# module.net
KiCad netlist of a schematic drawn in EAGLE
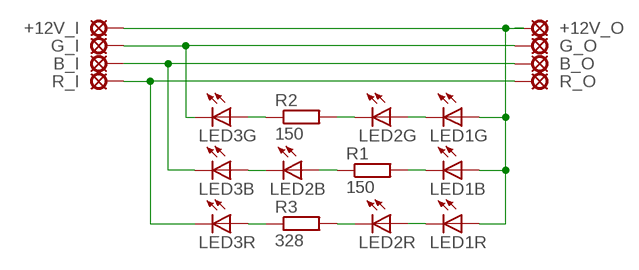
[diagram p0: schematic, sheet 1]

(export (version "E")
  (design (tool "Eeschema 10.0.6"))
  (components
    (comp (ref "+12V_I")
      (value "LSP10")
      (footprint "eagle-import:LSP10")
      (libsource (lib "eagle-import") (part "LSP10"))
    )
    (comp (ref "+12V_O")
      (value "LSP10")
      (footprint "eagle-import:LSP10")
      (libsource (lib "eagle-import") (part "LSP10"))
    )
    (comp (ref "B_I")
      (value "LSP10")
      (footprint "eagle-import:LSP10")
      (libsource (lib "eagle-import") (part "LSP10"))
    )
    (comp (ref "B_O")
      (value "LSP10")
      (footprint "eagle-import:LSP10")
      (libsource (lib "eagle-import") (part "LSP10"))
    )
    (comp (ref "G_I")
      (value "LSP10")
      (footprint "eagle-import:LSP10")
      (libsource (lib "eagle-import") (part "LSP10"))
    )
    (comp (ref "G_O")
      (value "LSP10")
      (footprint "eagle-import:LSP10")
      (libsource (lib "eagle-import") (part "LSP10"))
    )
    (comp (ref "LED1")
      (value "GM5WA94310A")
      (footprint "eagle-import:GM5WA94310A")
      (libsource (lib "eagle-import") (part "GM5WA94310A"))
    )
    (comp (ref "LED2")
      (value "GM5WA94310A")
      (footprint "eagle-import:GM5WA94310A")
      (libsource (lib "eagle-import") (part "GM5WA94310A"))
    )
    (comp (ref "LED3")
      (value "GM5WA94310A")
      (footprint "eagle-import:GM5WA94310A")
      (libsource (lib "eagle-import") (part "GM5WA94310A"))
    )
    (comp (ref "R1")
      (value "150")
      (footprint "eagle-import:M1206")
      (libsource (lib "eagle-import") (part "R-EU_M1206"))
    )
    (comp (ref "R2")
      (value "150")
      (footprint "eagle-import:M1206")
      (libsource (lib "eagle-import") (part "R-EU_M1206"))
    )
    (comp (ref "R3")
      (value "328")
      (footprint "eagle-import:M1206")
      (libsource (lib "eagle-import") (part "R-EU_M1206"))
    )
    (comp (ref "R_I")
      (value "LSP10")
      (footprint "eagle-import:LSP10")
      (libsource (lib "eagle-import") (part "LSP10"))
    )
    (comp (ref "R_O")
      (value "LSP10")
      (footprint "eagle-import:LSP10")
      (libsource (lib "eagle-import") (part "LSP10"))
    )
  )
  (nets
    (net (code "1") (name "Net-(LED1A-A)") (class "Default")
      (node (ref "+12V_I") (pin "MP") (pinfunction "MP_MP") (pintype "passive"))
      (node (ref "+12V_O") (pin "MP") (pinfunction "MP_MP") (pintype "passive"))
      (node (ref "LED1") (pin "1") (pinfunction "A_1") (pintype "passive"))
      (node (ref "LED1") (pin "2") (pinfunction "A_2") (pintype "passive"))
      (node (ref "LED1") (pin "3") (pinfunction "A_3") (pintype "passive"))
    )
    (net (code "2") (name "Net-(LED1A-C)") (class "Default")
      (node (ref "LED1") (pin "6") (pinfunction "C_6") (pintype "passive"))
      (node (ref "R1") (pin "2") (pinfunction "2_2") (pintype "passive"))
    )
    (net (code "3") (name "Net-(LED1B-C)") (class "Default")
      (node (ref "LED1") (pin "4") (pinfunction "C_4") (pintype "passive"))
      (node (ref "LED2") (pin "3") (pinfunction "A_3") (pintype "passive"))
    )
    (net (code "4") (name "Net-(LED1C-C)") (class "Default")
      (node (ref "LED1") (pin "5") (pinfunction "C_5") (pintype "passive"))
      (node (ref "LED2") (pin "2") (pinfunction "A_2") (pintype "passive"))
    )
    (net (code "5") (name "Net-(LED2A-A)") (class "Default")
      (node (ref "LED2") (pin "1") (pinfunction "A_1") (pintype "passive"))
      (node (ref "R1") (pin "1") (pinfunction "1_1") (pintype "passive"))
    )
    (net (code "6") (name "Net-(LED2A-C)") (class "Default")
      (node (ref "LED2") (pin "6") (pinfunction "C_6") (pintype "passive"))
      (node (ref "LED3") (pin "1") (pinfunction "A_1") (pintype "passive"))
    )
    (net (code "7") (name "Net-(LED2B-C)") (class "Default")
      (node (ref "LED2") (pin "4") (pinfunction "C_4") (pintype "passive"))
      (node (ref "R2") (pin "2") (pinfunction "2_2") (pintype "passive"))
    )
    (net (code "8") (name "Net-(LED2C-C)") (class "Default")
      (node (ref "LED2") (pin "5") (pinfunction "C_5") (pintype "passive"))
      (node (ref "R3") (pin "2") (pinfunction "2_2") (pintype "passive"))
    )
    (net (code "9") (name "Net-(LED3A-C)") (class "Default")
      (node (ref "B_I") (pin "MP") (pinfunction "MP_MP") (pintype "passive"))
      (node (ref "B_O") (pin "MP") (pinfunction "MP_MP") (pintype "passive"))
      (node (ref "LED3") (pin "6") (pinfunction "C_6") (pintype "passive"))
    )
    (net (code "10") (name "Net-(LED3B-A)") (class "Default")
      (node (ref "LED3") (pin "3") (pinfunction "A_3") (pintype "passive"))
      (node (ref "R2") (pin "1") (pinfunction "1_1") (pintype "passive"))
    )
    (net (code "11") (name "Net-(LED3B-C)") (class "Default")
      (node (ref "G_I") (pin "MP") (pinfunction "MP_MP") (pintype "passive"))
      (node (ref "G_O") (pin "MP") (pinfunction "MP_MP") (pintype "passive"))
      (node (ref "LED3") (pin "4") (pinfunction "C_4") (pintype "passive"))
    )
    (net (code "12") (name "Net-(LED3C-A)") (class "Default")
      (node (ref "LED3") (pin "2") (pinfunction "A_2") (pintype "passive"))
      (node (ref "R3") (pin "1") (pinfunction "1_1") (pintype "passive"))
    )
    (net (code "13") (name "Net-(LED3C-C)") (class "Default")
      (node (ref "LED3") (pin "5") (pinfunction "C_5") (pintype "passive"))
      (node (ref "R_I") (pin "MP") (pinfunction "MP_MP") (pintype "passive"))
      (node (ref "R_O") (pin "MP") (pinfunction "MP_MP") (pintype "passive"))
    )
  )
)
